# Digital_Greippi.net
KiCad netlist of a schematic drawn in EAGLE
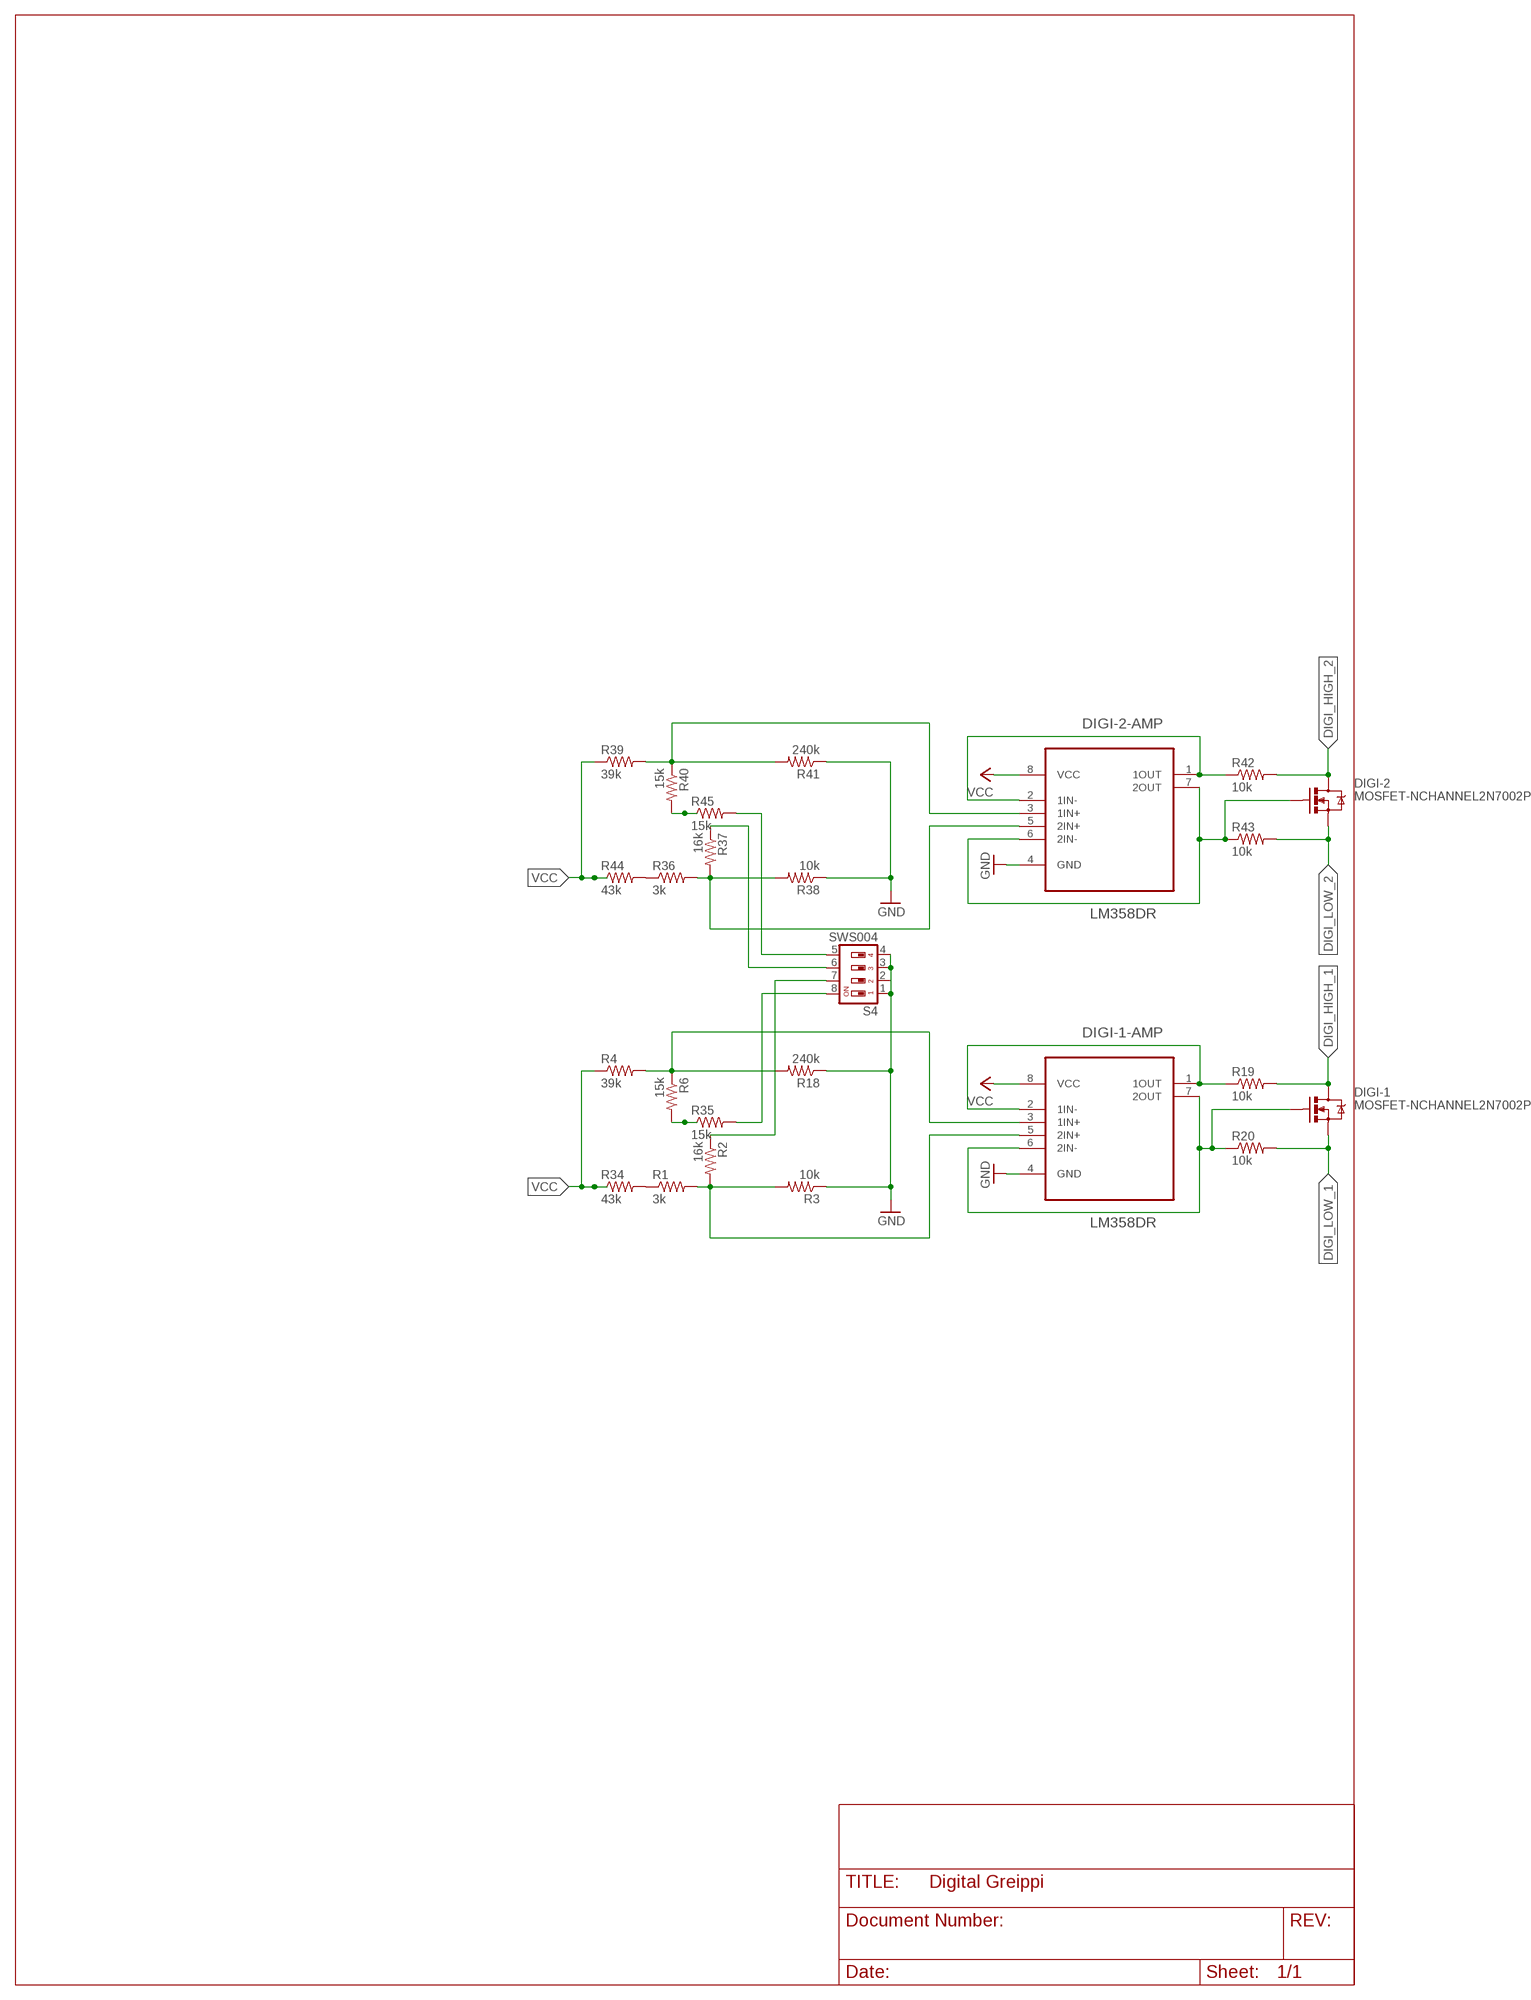
[diagram p0: schematic, sheet 1]

(export (version "E")
  (design (tool "Eeschema 10.0.6"))
  (components
    (comp (ref "DIGI-1")
      (value "MOSFET-NCHANNEL2N7002PW")
      (footprint "eagle-import:SOT323")
      (libsource (lib "eagle-import") (part "MOSFET-NCHANNEL2N7002PW"))
    )
    (comp (ref "DIGI-1-AMP")
      (value "LM358DR")
      (footprint "eagle-import:SOIC127P600X175-8N")
      (libsource (lib "eagle-import") (part "LM358DR"))
    )
    (comp (ref "DIGI-2")
      (value "MOSFET-NCHANNEL2N7002PW")
      (footprint "eagle-import:SOT323")
      (libsource (lib "eagle-import") (part "MOSFET-NCHANNEL2N7002PW"))
    )
    (comp (ref "DIGI-2-AMP")
      (value "LM358DR")
      (footprint "eagle-import:SOIC127P600X175-8N")
      (libsource (lib "eagle-import") (part "LM358DR"))
    )
    (comp (ref "R1")
      (value "3k")
      (footprint "eagle-import:R0805")
      (libsource (lib "eagle-import") (part "R-US_R0805"))
    )
    (comp (ref "R2")
      (value "16k")
      (footprint "eagle-import:R0805")
      (libsource (lib "eagle-import") (part "R-US_R0805"))
    )
    (comp (ref "R3")
      (value "10k")
      (footprint "eagle-import:R0805")
      (libsource (lib "eagle-import") (part "R-US_R0805"))
    )
    (comp (ref "R4")
      (value "39k")
      (footprint "eagle-import:R0805")
      (libsource (lib "eagle-import") (part "R-US_R0805"))
    )
    (comp (ref "R6")
      (value "15k")
      (footprint "eagle-import:R0805")
      (libsource (lib "eagle-import") (part "R-US_R0805"))
    )
    (comp (ref "R18")
      (value "240k")
      (footprint "eagle-import:R0805")
      (libsource (lib "eagle-import") (part "R-US_R0805"))
    )
    (comp (ref "R19")
      (value "10k")
      (footprint "eagle-import:R0805")
      (libsource (lib "eagle-import") (part "R-US_R0805"))
    )
    (comp (ref "R20")
      (value "10k")
      (footprint "eagle-import:R0805")
      (libsource (lib "eagle-import") (part "R-US_R0805"))
    )
    (comp (ref "R34")
      (value "43k")
      (footprint "eagle-import:R0805")
      (libsource (lib "eagle-import") (part "R-US_R0805"))
    )
    (comp (ref "R35")
      (value "15k")
      (footprint "eagle-import:R0805")
      (libsource (lib "eagle-import") (part "R-US_R0805"))
    )
    (comp (ref "R36")
      (value "3k")
      (footprint "eagle-import:R0805")
      (libsource (lib "eagle-import") (part "R-US_R0805"))
    )
    (comp (ref "R37")
      (value "16k")
      (footprint "eagle-import:R0805")
      (libsource (lib "eagle-import") (part "R-US_R0805"))
    )
    (comp (ref "R38")
      (value "10k")
      (footprint "eagle-import:R0805")
      (libsource (lib "eagle-import") (part "R-US_R0805"))
    )
    (comp (ref "R39")
      (value "39k")
      (footprint "eagle-import:R0805")
      (libsource (lib "eagle-import") (part "R-US_R0805"))
    )
    (comp (ref "R40")
      (value "15k")
      (footprint "eagle-import:R0805")
      (libsource (lib "eagle-import") (part "R-US_R0805"))
    )
    (comp (ref "R41")
      (value "240k")
      (footprint "eagle-import:R0805")
      (libsource (lib "eagle-import") (part "R-US_R0805"))
    )
    (comp (ref "R42")
      (value "10k")
      (footprint "eagle-import:R0805")
      (libsource (lib "eagle-import") (part "R-US_R0805"))
    )
    (comp (ref "R43")
      (value "10k")
      (footprint "eagle-import:R0805")
      (libsource (lib "eagle-import") (part "R-US_R0805"))
    )
    (comp (ref "R44")
      (value "43k")
      (footprint "eagle-import:R0805")
      (libsource (lib "eagle-import") (part "R-US_R0805"))
    )
    (comp (ref "R45")
      (value "15k")
      (footprint "eagle-import:R0805")
      (libsource (lib "eagle-import") (part "R-US_R0805"))
    )
    (comp (ref "S4")
      (value "SWS004")
      (footprint "eagle-import:SMS-004")
      (libsource (lib "eagle-import") (part "SWS004"))
    )
  )
  (nets
    (net (code "1") (name "DIGI_HIGH_1") (class "Default")
      (node (ref "DIGI-1") (pin "3") (pinfunction "D_3") (pintype "passive"))
      (node (ref "R19") (pin "2") (pinfunction "2_2") (pintype "passive"))
    )
    (net (code "2") (name "DIGI_HIGH_2") (class "Default")
      (node (ref "DIGI-2") (pin "3") (pinfunction "D_3") (pintype "passive"))
      (node (ref "R42") (pin "2") (pinfunction "2_2") (pintype "passive"))
    )
    (net (code "3") (name "DIGI_LOW_1") (class "Default")
      (node (ref "DIGI-1") (pin "2") (pinfunction "S_2") (pintype "passive"))
      (node (ref "R20") (pin "2") (pinfunction "2_2") (pintype "passive"))
    )
    (net (code "4") (name "DIGI_LOW_2") (class "Default")
      (node (ref "DIGI-2") (pin "2") (pinfunction "S_2") (pintype "passive"))
      (node (ref "R43") (pin "2") (pinfunction "2_2") (pintype "passive"))
    )
    (net (code "5") (name "GND") (class "Default")
      (node (ref "DIGI-1-AMP") (pin "4") (pinfunction "GND_4") (pintype "passive"))
      (node (ref "DIGI-2-AMP") (pin "4") (pinfunction "GND_4") (pintype "passive"))
      (node (ref "R18") (pin "1") (pinfunction "1_1") (pintype "passive"))
      (node (ref "R3") (pin "1") (pinfunction "1_1") (pintype "passive"))
      (node (ref "R38") (pin "1") (pinfunction "1_1") (pintype "passive"))
      (node (ref "R41") (pin "1") (pinfunction "1_1") (pintype "passive"))
      (node (ref "S4") (pin "1") (pinfunction "1_1") (pintype "passive"))
      (node (ref "S4") (pin "2") (pinfunction "2_2") (pintype "passive"))
      (node (ref "S4") (pin "3") (pinfunction "3_3") (pintype "passive"))
      (node (ref "S4") (pin "4") (pinfunction "4_4") (pintype "passive"))
    )
    (net (code "6") (name "Net-(DIGI-1-AMP-1IN+)") (class "Default")
      (node (ref "DIGI-1-AMP") (pin "3") (pinfunction "1IN+_3") (pintype "input"))
      (node (ref "R18") (pin "2") (pinfunction "2_2") (pintype "passive"))
      (node (ref "R4") (pin "2") (pinfunction "2_2") (pintype "passive"))
      (node (ref "R6") (pin "1") (pinfunction "1_1") (pintype "passive"))
    )
    (net (code "7") (name "Net-(DIGI-1-AMP-1IN-)") (class "Default")
      (node (ref "DIGI-1-AMP") (pin "1") (pinfunction "1OUT_1") (pintype "output"))
      (node (ref "DIGI-1-AMP") (pin "2") (pinfunction "1IN-_2") (pintype "input"))
      (node (ref "R19") (pin "1") (pinfunction "1_1") (pintype "passive"))
    )
    (net (code "8") (name "Net-(DIGI-1-AMP-2IN+)") (class "Default")
      (node (ref "DIGI-1-AMP") (pin "5") (pinfunction "2IN+_5") (pintype "input"))
      (node (ref "R1") (pin "2") (pinfunction "2_2") (pintype "passive"))
      (node (ref "R2") (pin "2") (pinfunction "2_2") (pintype "passive"))
      (node (ref "R3") (pin "2") (pinfunction "2_2") (pintype "passive"))
    )
    (net (code "9") (name "Net-(DIGI-1-AMP-2IN-)") (class "Default")
      (node (ref "DIGI-1") (pin "1") (pinfunction "G_1") (pintype "passive"))
      (node (ref "DIGI-1-AMP") (pin "6") (pinfunction "2IN-_6") (pintype "input"))
      (node (ref "DIGI-1-AMP") (pin "7") (pinfunction "2OUT_7") (pintype "output"))
      (node (ref "R20") (pin "1") (pinfunction "1_1") (pintype "passive"))
    )
    (net (code "10") (name "Net-(DIGI-2-AMP-1IN+)") (class "Default")
      (node (ref "DIGI-2-AMP") (pin "3") (pinfunction "1IN+_3") (pintype "input"))
      (node (ref "R39") (pin "2") (pinfunction "2_2") (pintype "passive"))
      (node (ref "R40") (pin "1") (pinfunction "1_1") (pintype "passive"))
      (node (ref "R41") (pin "2") (pinfunction "2_2") (pintype "passive"))
    )
    (net (code "11") (name "Net-(DIGI-2-AMP-1IN-)") (class "Default")
      (node (ref "DIGI-2-AMP") (pin "1") (pinfunction "1OUT_1") (pintype "output"))
      (node (ref "DIGI-2-AMP") (pin "2") (pinfunction "1IN-_2") (pintype "input"))
      (node (ref "R42") (pin "1") (pinfunction "1_1") (pintype "passive"))
    )
    (net (code "12") (name "Net-(DIGI-2-AMP-2IN+)") (class "Default")
      (node (ref "DIGI-2-AMP") (pin "5") (pinfunction "2IN+_5") (pintype "input"))
      (node (ref "R36") (pin "2") (pinfunction "2_2") (pintype "passive"))
      (node (ref "R37") (pin "2") (pinfunction "2_2") (pintype "passive"))
      (node (ref "R38") (pin "2") (pinfunction "2_2") (pintype "passive"))
    )
    (net (code "13") (name "Net-(DIGI-2-AMP-2IN-)") (class "Default")
      (node (ref "DIGI-2") (pin "1") (pinfunction "G_1") (pintype "passive"))
      (node (ref "DIGI-2-AMP") (pin "6") (pinfunction "2IN-_6") (pintype "input"))
      (node (ref "DIGI-2-AMP") (pin "7") (pinfunction "2OUT_7") (pintype "output"))
      (node (ref "R43") (pin "1") (pinfunction "1_1") (pintype "passive"))
    )
    (net (code "14") (name "Net-(R1-Pad1)") (class "Default")
      (node (ref "R1") (pin "1") (pinfunction "1_1") (pintype "passive"))
      (node (ref "R34") (pin "2") (pinfunction "2_2") (pintype "passive"))
    )
    (net (code "15") (name "Net-(R2-Pad1)") (class "Default")
      (node (ref "R2") (pin "1") (pinfunction "1_1") (pintype "passive"))
      (node (ref "S4") (pin "7") (pinfunction "7_7") (pintype "passive"))
    )
    (net (code "16") (name "Net-(R35-Pad1)") (class "Default")
      (node (ref "R35") (pin "1") (pinfunction "1_1") (pintype "passive"))
      (node (ref "R6") (pin "2") (pinfunction "2_2") (pintype "passive"))
    )
    (net (code "17") (name "Net-(R35-Pad2)") (class "Default")
      (node (ref "R35") (pin "2") (pinfunction "2_2") (pintype "passive"))
      (node (ref "S4") (pin "8") (pinfunction "8_8") (pintype "passive"))
    )
    (net (code "18") (name "Net-(R36-Pad1)") (class "Default")
      (node (ref "R36") (pin "1") (pinfunction "1_1") (pintype "passive"))
      (node (ref "R44") (pin "2") (pinfunction "2_2") (pintype "passive"))
    )
    (net (code "19") (name "Net-(R37-Pad1)") (class "Default")
      (node (ref "R37") (pin "1") (pinfunction "1_1") (pintype "passive"))
      (node (ref "S4") (pin "6") (pinfunction "6_6") (pintype "passive"))
    )
    (net (code "20") (name "Net-(R40-Pad2)") (class "Default")
      (node (ref "R40") (pin "2") (pinfunction "2_2") (pintype "passive"))
      (node (ref "R45") (pin "1") (pinfunction "1_1") (pintype "passive"))
    )
    (net (code "21") (name "Net-(R45-Pad2)") (class "Default")
      (node (ref "R45") (pin "2") (pinfunction "2_2") (pintype "passive"))
      (node (ref "S4") (pin "5") (pinfunction "5_5") (pintype "passive"))
    )
    (net (code "22") (name "VCC") (class "Default")
      (node (ref "DIGI-1-AMP") (pin "8") (pinfunction "VCC_8") (pintype "power_in"))
      (node (ref "DIGI-2-AMP") (pin "8") (pinfunction "VCC_8") (pintype "power_in"))
      (node (ref "R34") (pin "1") (pinfunction "1_1") (pintype "passive"))
      (node (ref "R39") (pin "1") (pinfunction "1_1") (pintype "passive"))
      (node (ref "R4") (pin "1") (pinfunction "1_1") (pintype "passive"))
      (node (ref "R44") (pin "1") (pinfunction "1_1") (pintype "passive"))
    )
  )
)
